# Schematic.net
KiCad netlist of a schematic drawn in Altium Designer
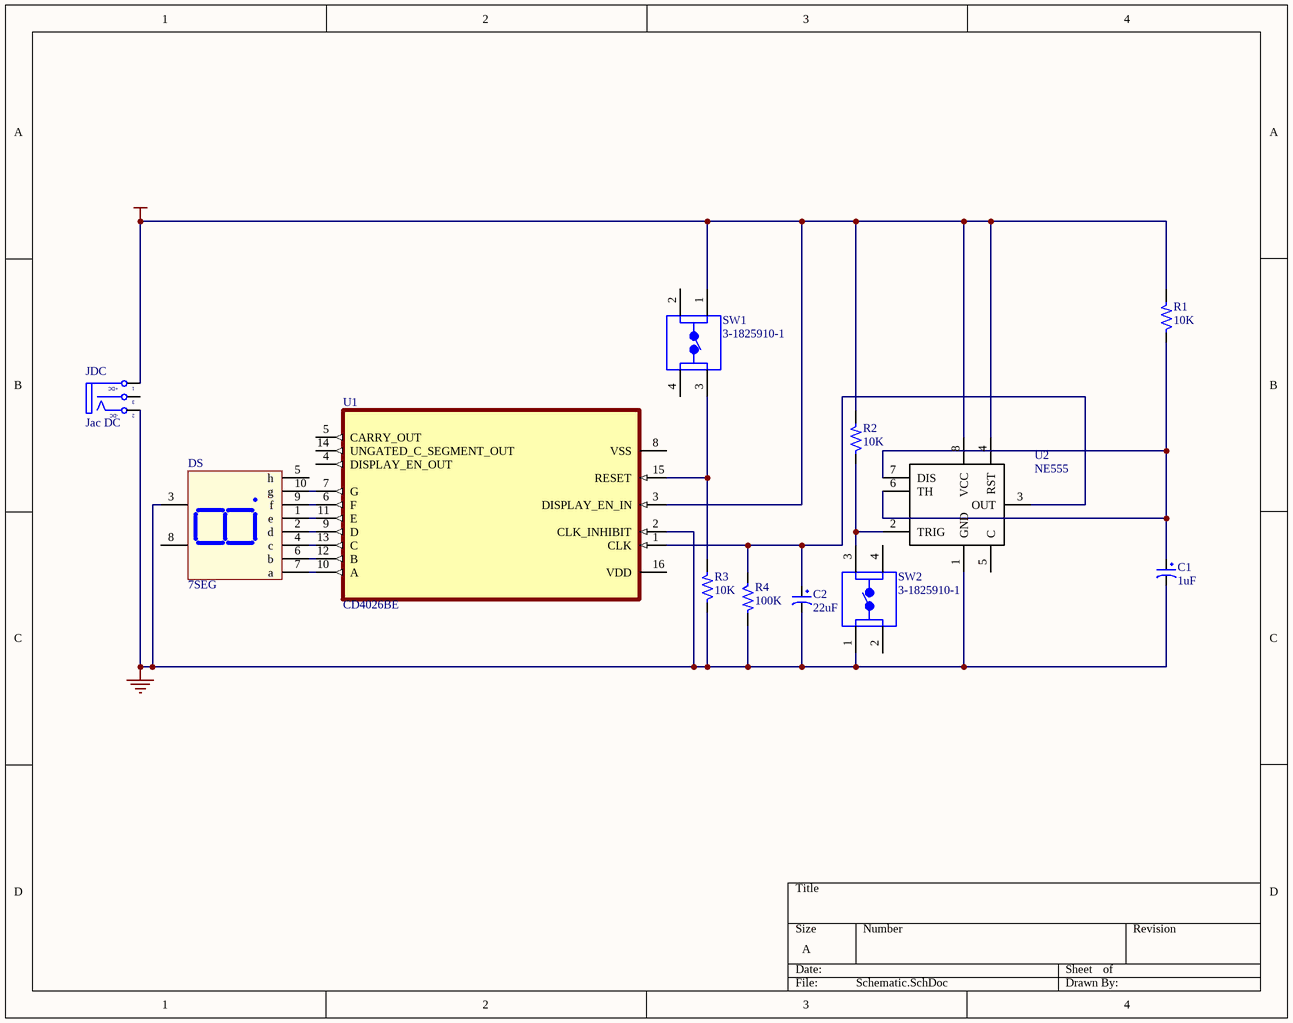
[diagram p0: Schematic.SchDoc]

(export (version "E")
  (design (tool "Eeschema 10.0.6"))
  (components
    (comp (ref "C1")
      (value "1uF")
      (footprint "CP1/2")
      (description "Cap P  0,1uF < 22uF , 16 - 50V")
      (libsource (lib "echipkool-com-library") (part "CP1"))
    )
    (comp (ref "C2")
      (value "22uF")
      (footprint "CP1/2")
      (description "Cap P  0,1uF < 22uF , 16 - 50V")
      (libsource (lib "echipkool-com-library") (part "CP1"))
    )
    (comp (ref "DS")
      (value "7SEG")
      (footprint "LED7SEG-1-0.56")
      (description "14.2 mm General Purpose Blue 7-Segment Display: CC, RH DP, Gray Surface")
      (fields (field (name "PUBLISHER") "Altium Limited"))
      (libsource (lib "LIBRARYALT") (part "LED7SEG-1"))
    )
    (comp (ref "JDC")
      (value "Jac DC")
      (footprint "DC0")
      (description "Jac DC input")
      (libsource (lib "LIBRARYALT") (part "DCIN"))
    )
    (comp (ref "R1")
      (value "10K")
      (footprint "R1/4W")
      (description "Resistor 1/4W")
      (libsource (lib "echipkool-com-library") (part "R"))
    )
    (comp (ref "R2")
      (value "10K")
      (footprint "R1/4W")
      (description "Resistor 1/4W")
      (libsource (lib "echipkool-com-library") (part "R"))
    )
    (comp (ref "R3")
      (value "10K")
      (footprint "R1/4W")
      (description "Resistor 1/4W")
      (libsource (lib "echipkool-com-library") (part "R"))
    )
    (comp (ref "R4")
      (value "100K")
      (footprint "R1/4W")
      (description "Resistor 1/4W")
      (libsource (lib "echipkool-com-library") (part "R"))
    )
    (comp (ref "SW1")
      (value "3-1825910-1")
      (footprint "TE_3-1825910-1")
      (description "Switch Push Button OFF _ON_ SPST Round Button 0.05A 24VDC Momentary Contact PC Pins Thru-Hole")
      (fields (field (name "MF") "TE Connectivity"))
      (libsource (lib "SnapEDAsch") (part "3-1825910-1"))
    )
    (comp (ref "SW2")
      (value "3-1825910-1")
      (footprint "TE_3-1825910-1")
      (description "Switch Push Button OFF _ON_ SPST Round Button 0.05A 24VDC Momentary Contact PC Pins Thru-Hole")
      (fields (field (name "MF") "TE Connectivity"))
      (libsource (lib "SnapEDAsch") (part "3-1825910-1"))
    )
    (comp (ref "U1")
      (value "CD4026BE")
      (footprint "DIP254P762X508-16")
      (description "Counter IC Counter, Decade 1 Element 5 Bit Positive Edge 16-PDIP")
      (fields (field (name "MF") "Texas Instruments"))
      (libsource (lib "CD4026BE") (part "CD4026BE"))
    )
    (comp (ref "U2")
      (value "NE555")
      (footprint "DIP8")
      (description "TIMER IC")
      (fields
        (field (name "MANUFACTURER PART NUMBER") "NE555DT")
        (field (name "MANUFACTURER") "STMicroelectronics")
      )
      (libsource (lib "LIBRARYALT") (part "NE555"))
    )
  )
  (nets
    (net (code "1") (name "+5") (class "Default")
      (node (ref "JDC") (pin "1") (pinfunction "T_1") (pintype "passive"))
      (node (ref "R1") (pin "2") (pinfunction "2_2") (pintype "passive"))
      (node (ref "R2") (pin "2") (pinfunction "2_2") (pintype "passive"))
      (node (ref "SW1") (pin "1") (pinfunction "1_1") (pintype "passive"))
      (node (ref "U1") (pin "3") (pinfunction "DISPLAY_EN_IN_3") (pintype "input"))
      (node (ref "U2") (pin "4") (pinfunction "RST_4") (pintype "passive"))
      (node (ref "U2") (pin "8") (pinfunction "VCC_8") (pintype "passive"))
    )
    (net (code "2") (name "GND") (class "Default")
      (node (ref "C1") (pin "2") (pinfunction "2_2") (pintype "passive"))
      (node (ref "C2") (pin "2") (pinfunction "2_2") (pintype "passive"))
      (node (ref "DS") (pin "3") (pinfunction "Vcc_3") (pintype "passive"))
      (node (ref "JDC") (pin "2") (pinfunction "TN_2") (pintype "passive"))
      (node (ref "R3") (pin "1") (pinfunction "1_1") (pintype "passive"))
      (node (ref "R4") (pin "2") (pinfunction "2_2") (pintype "passive"))
      (node (ref "SW2") (pin "1") (pinfunction "1_1") (pintype "passive"))
      (node (ref "U1") (pin "2") (pinfunction "CLK_INHIBIT_2") (pintype "input"))
      (node (ref "U2") (pin "1") (pinfunction "GND_1") (pintype "passive"))
    )
    (net (code "3") (name "Net-(DS-a)") (class "Default")
      (node (ref "DS") (pin "7") (pinfunction "a_7") (pintype "passive"))
      (node (ref "U1") (pin "10") (pinfunction "A_10") (pintype "output"))
    )
    (net (code "4") (name "Net-(DS-b)") (class "Default")
      (node (ref "DS") (pin "6") (pinfunction "b_6") (pintype "passive"))
      (node (ref "U1") (pin "12") (pinfunction "B_12") (pintype "output"))
    )
    (net (code "5") (name "Net-(DS-c)") (class "Default")
      (node (ref "DS") (pin "4") (pinfunction "c_4") (pintype "passive"))
      (node (ref "U1") (pin "13") (pinfunction "C_13") (pintype "output"))
    )
    (net (code "6") (name "Net-(DS-d)") (class "Default")
      (node (ref "DS") (pin "2") (pinfunction "d_2") (pintype "passive"))
      (node (ref "U1") (pin "9") (pinfunction "D_9") (pintype "output"))
    )
    (net (code "7") (name "Net-(DS-e)") (class "Default")
      (node (ref "DS") (pin "1") (pinfunction "e_1") (pintype "passive"))
      (node (ref "U1") (pin "11") (pinfunction "E_11") (pintype "output"))
    )
    (net (code "8") (name "Net-(DS-f)") (class "Default")
      (node (ref "DS") (pin "9") (pinfunction "f_9") (pintype "passive"))
      (node (ref "U1") (pin "6") (pinfunction "F_6") (pintype "output"))
    )
    (net (code "9") (name "Net-(DS-g)") (class "Default")
      (node (ref "DS") (pin "10") (pinfunction "g_10") (pintype "passive"))
      (node (ref "U1") (pin "7") (pinfunction "G_7") (pintype "output"))
    )
    (net (code "10") (name "Net-(U1-CLK)") (class "Default")
      (node (ref "C2") (pin "1") (pinfunction "1_1") (pintype "passive"))
      (node (ref "R4") (pin "1") (pinfunction "1_1") (pintype "passive"))
      (node (ref "U1") (pin "1") (pinfunction "CLK_1") (pintype "input"))
      (node (ref "U2") (pin "3") (pinfunction "OUT_3") (pintype "passive"))
    )
    (net (code "11") (name "Net-(U1-RESET)") (class "Default")
      (node (ref "R3") (pin "2") (pinfunction "2_2") (pintype "passive"))
      (node (ref "SW1") (pin "3") (pinfunction "3_3") (pintype "passive"))
      (node (ref "U1") (pin "15") (pinfunction "RESET_15") (pintype "input"))
    )
    (net (code "12") (name "Net-(U2-DIS)") (class "Default")
      (node (ref "C1") (pin "1") (pinfunction "1_1") (pintype "passive"))
      (node (ref "R1") (pin "1") (pinfunction "1_1") (pintype "passive"))
      (node (ref "U2") (pin "6") (pinfunction "TH_6") (pintype "passive"))
      (node (ref "U2") (pin "7") (pinfunction "DIS_7") (pintype "passive"))
    )
    (net (code "13") (name "Net-(U2-TRIG)") (class "Default")
      (node (ref "R2") (pin "1") (pinfunction "1_1") (pintype "passive"))
      (node (ref "SW2") (pin "3") (pinfunction "3_3") (pintype "passive"))
      (node (ref "U2") (pin "2") (pinfunction "TRIG_2") (pintype "passive"))
    )
    (net (code "14") (name "unconnected-(DS-Vcc-Pad8)") (class "Default")
      (node (ref "DS") (pin "8") (pinfunction "Vcc_8") (pintype "passive"))
    )
    (net (code "15") (name "unconnected-(DS-h-Pad5)") (class "Default")
      (node (ref "DS") (pin "5") (pinfunction "h_5") (pintype "passive"))
    )
    (net (code "16") (name "unconnected-(JDC-S-Pad3)") (class "Default")
      (node (ref "JDC") (pin "3") (pinfunction "S_3") (pintype "power_in"))
    )
    (net (code "17") (name "unconnected-(SW1-Pad2)") (class "Default")
      (node (ref "SW1") (pin "2") (pinfunction "2_2") (pintype "passive"))
    )
    (net (code "18") (name "unconnected-(SW1-Pad4)") (class "Default")
      (node (ref "SW1") (pin "4") (pinfunction "4_4") (pintype "passive"))
    )
    (net (code "19") (name "unconnected-(SW2-Pad2)") (class "Default")
      (node (ref "SW2") (pin "2") (pinfunction "2_2") (pintype "passive"))
    )
    (net (code "20") (name "unconnected-(SW2-Pad4)") (class "Default")
      (node (ref "SW2") (pin "4") (pinfunction "4_4") (pintype "passive"))
    )
    (net (code "21") (name "unconnected-(U1-CARRY_OUT-Pad5)") (class "Default")
      (node (ref "U1") (pin "5") (pinfunction "CARRY_OUT_5") (pintype "output"))
    )
    (net (code "22") (name "unconnected-(U1-DISPLAY_EN_OUT-Pad4)") (class "Default")
      (node (ref "U1") (pin "4") (pinfunction "DISPLAY_EN_OUT_4") (pintype "output"))
    )
    (net (code "23") (name "unconnected-(U1-UNGATED_C_SEGMENT_OUT-Pad14)") (class "Default")
      (node (ref "U1") (pin "14") (pinfunction "UNGATED_C_SEGMENT_OUT_14") (pintype "output"))
    )
    (net (code "24") (name "unconnected-(U1-VDD-Pad16)") (class "Default")
      (node (ref "U1") (pin "16") (pinfunction "VDD_16") (pintype "power_in"))
    )
    (net (code "25") (name "unconnected-(U1-VSS-Pad8)") (class "Default")
      (node (ref "U1") (pin "8") (pinfunction "VSS_8") (pintype "power_in"))
    )
    (net (code "26") (name "unconnected-(U2-C-Pad5)") (class "Default")
      (node (ref "U2") (pin "5") (pinfunction "C_5") (pintype "passive"))
    )
  )
)
